# crypto_blk.net
KiCad netlist of a schematic drawn in Altium Designer
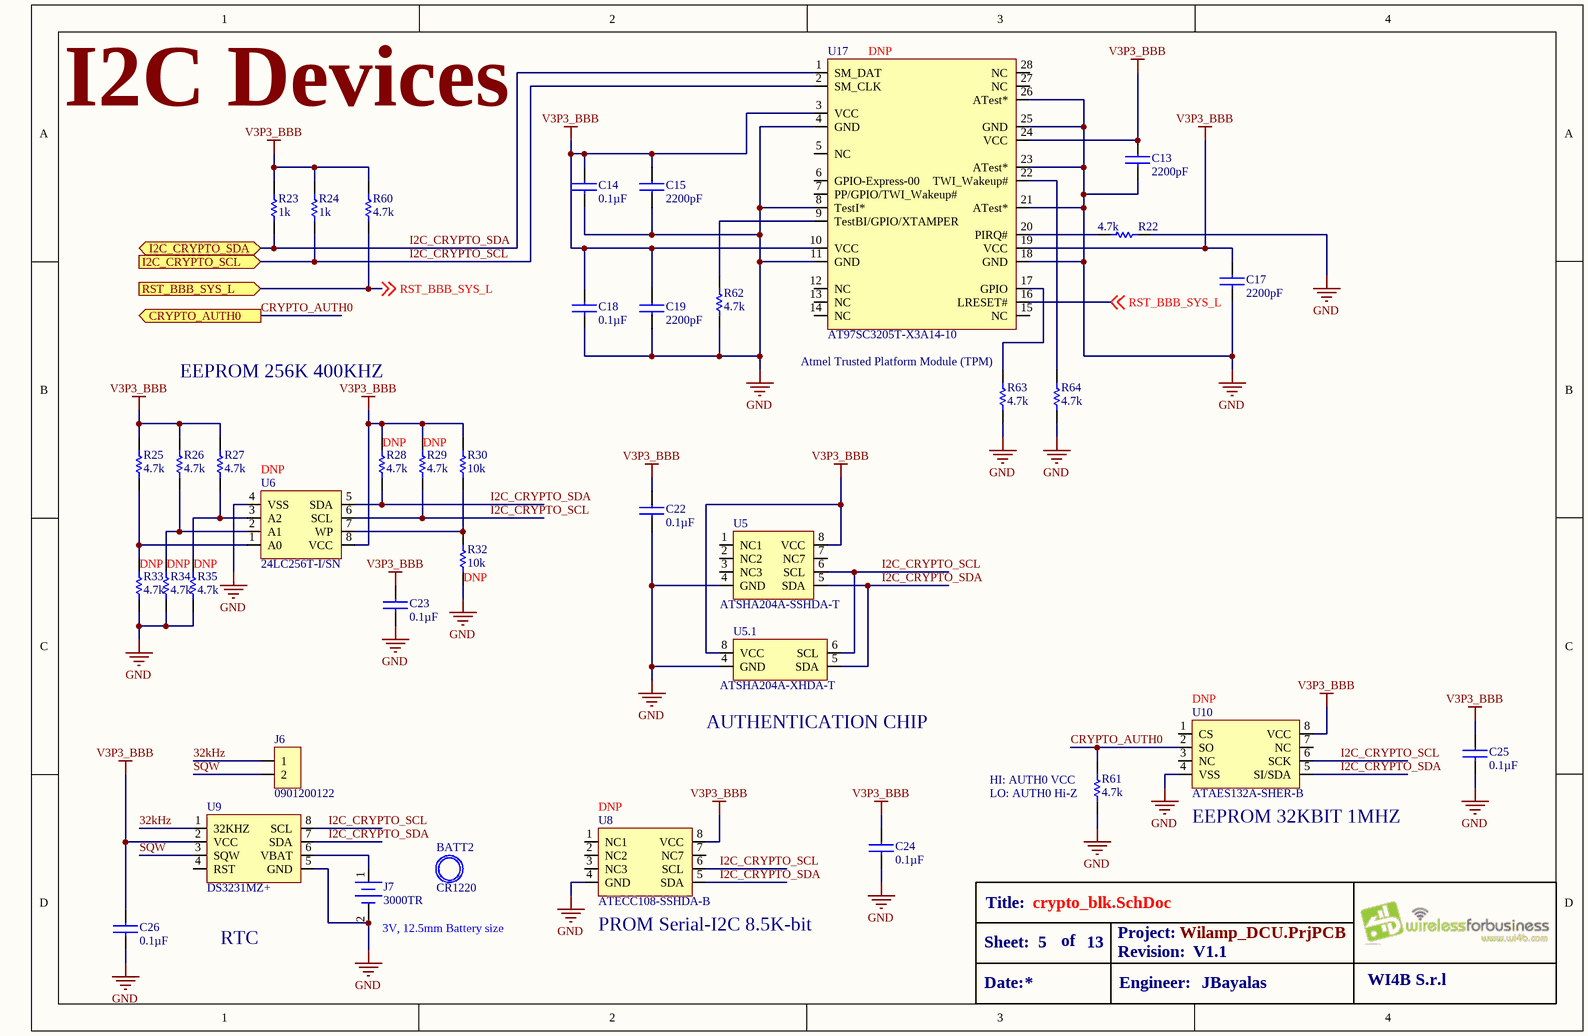
[diagram p0: crypto_blk.SchDoc]

(export (version "E")
  (design (tool "Eeschema 10.0.6"))
  (components
    (comp (ref "BATT2")
      (value "CR1220")
      (description "Coin Cell Battery 35mAh 12.5mm")
      (fields (field (name "MPN") "CR1220"))
      (libsource (lib "Miscellaneous") (part "CR1220"))
    )
    (comp (ref "C13")
      (value "2200pF")
      (footprint "C0805")
      (description "CAP CER 2200PF 50V 10% X7R 0805")
      (fields (field (name "MPN") "08055C222KAT2A"))
      (libsource (lib "Capacitor") (part "08055C222KAT2A"))
    )
    (comp (ref "C14")
      (value "0.1µF")
      (footprint "C0402")
      (description "CAP CER 0.1UF 16V X7R 0402")
      (fields (field (name "MPN") "CL05B104KO3LNNC"))
      (libsource (lib "Capacitor") (part "CL05B104KO3LNNC"))
    )
    (comp (ref "C15")
      (value "2200pF")
      (footprint "C0805")
      (description "CAP CER 2200PF 50V 10% X7R 0805")
      (fields (field (name "MPN") "08055C222KAT2A"))
      (libsource (lib "Capacitor") (part "08055C222KAT2A"))
    )
    (comp (ref "C17")
      (value "2200pF")
      (footprint "C0603")
      (description "CAP CER 2200PF 50V X7R 0603")
      (fields (field (name "MPN") "C0603C222K5RACTU"))
      (libsource (lib "Capacitor") (part "C0603C222K5RACTU"))
    )
    (comp (ref "C18")
      (value "0.1µF")
      (footprint "C0402")
      (description "CAP CER 0.1UF 16V X7R 0402")
      (fields (field (name "MPN") "CL05B104KO3LNNC"))
      (libsource (lib "Capacitor") (part "CL05B104KO3LNNC"))
    )
    (comp (ref "C19")
      (value "2200pF")
      (footprint "C0805")
      (description "CAP CER 2200PF 50V 10% X7R 0805")
      (fields (field (name "MPN") "08055C222KAT2A"))
      (libsource (lib "Capacitor") (part "08055C222KAT2A"))
    )
    (comp (ref "C22")
      (value "0.1µF")
      (footprint "C0402")
      (description "CAP CER 0.1UF 16V X7R 0402")
      (fields (field (name "MPN") "CL05B104KO3LNNC"))
      (libsource (lib "Capacitor") (part "CL05B104KO3LNNC"))
    )
    (comp (ref "C23")
      (value "0.1µF")
      (footprint "C0402")
      (description "CAP CER 0.1UF 16V X7R 0402")
      (fields (field (name "MPN") "CL05B104KO3LNNC"))
      (libsource (lib "Capacitor") (part "CL05B104KO3LNNC"))
    )
    (comp (ref "C24")
      (value "0.1µF")
      (footprint "C0402")
      (description "CAP CER 0.1UF 16V X7R 0402")
      (fields (field (name "MPN") "CL05B104KO3LNNC"))
      (libsource (lib "Capacitor") (part "CL05B104KO3LNNC"))
    )
    (comp (ref "C25")
      (value "0.1µF")
      (footprint "C0402")
      (description "CAP CER 0.1UF 16V X7R 0402")
      (fields (field (name "MPN") "CL05B104KO3LNNC"))
      (libsource (lib "Capacitor") (part "CL05B104KO3LNNC"))
    )
    (comp (ref "C26")
      (value "0.1µF")
      (footprint "C0402")
      (description "CAP CER 0.1UF 16V X7R 0402")
      (fields (field (name "MPN") "CL05B104KO3LNNC"))
      (libsource (lib "Capacitor") (part "CL05B104KO3LNNC"))
    )
    (comp (ref "J6")
      (value "*")
      (footprint "0901200122")
      (description "CONN HEADER 2POS .100\" STR TIN")
      (fields (field (name "MPN") "0901200122"))
      (libsource (lib "Connector") (part "0901200122"))
    )
    (comp (ref "J7")
      (value "3000TR")
      (footprint "3000TR")
      (description "Coin Cell Battery Holders SM COIN CELL B/H")
      (libsource (lib "Connector") (part "3000TR"))
    )
    (comp (ref "R22")
      (value "4.7k")
      (footprint "R0402")
      (description "RES SMD 4.7K OHM 5% 1/16W 0402")
      (fields (field (name "MPN") "RC0402JR-074K7L"))
      (libsource (lib "Res") (part "RC0402JR-074K7L"))
    )
    (comp (ref "R23")
      (value "1k")
      (footprint "R0402")
      (description "RES SMD 1K OHM 1% 1/10W 0402")
      (fields (field (name "MPN") "MCS04020C1001FE000"))
      (libsource (lib "Res") (part "MCS04020C1001FE000"))
    )
    (comp (ref "R24")
      (value "1k")
      (footprint "R0402")
      (description "RES SMD 1K OHM 1% 1/10W 0402")
      (fields (field (name "MPN") "MCS04020C1001FE000"))
      (libsource (lib "Res") (part "MCS04020C1001FE000"))
    )
    (comp (ref "R25")
      (value "4.7k")
      (footprint "R0402")
      (description "RES SMD 4.7K OHM 5% 1/16W 0402")
      (fields (field (name "MPN") "RC0402JR-074K7L"))
      (libsource (lib "Res") (part "RC0402JR-074K7L"))
    )
    (comp (ref "R26")
      (value "4.7k")
      (footprint "R0402")
      (description "RES SMD 4.7K OHM 5% 1/16W 0402")
      (fields (field (name "MPN") "RC0402JR-074K7L"))
      (libsource (lib "Res") (part "RC0402JR-074K7L"))
    )
    (comp (ref "R27")
      (value "4.7k")
      (footprint "R0402")
      (description "RES SMD 4.7K OHM 5% 1/16W 0402")
      (fields (field (name "MPN") "RC0402JR-074K7L"))
      (libsource (lib "Res") (part "RC0402JR-074K7L"))
    )
    (comp (ref "R28")
      (value "4.7k")
      (footprint "R0402")
      (description "RES SMD 4.7K OHM 5% 1/16W 0402")
      (fields (field (name "MPN") "RC0402JR-074K7L") (field (name "LOAD") "DNP"))
      (libsource (lib "Res") (part "RC0402JR-074K7L"))
    )
    (comp (ref "R29")
      (value "4.7k")
      (footprint "R0402")
      (description "RES SMD 4.7K OHM 5% 1/16W 0402")
      (fields (field (name "MPN") "RC0402JR-074K7L") (field (name "LOAD") "DNP"))
      (libsource (lib "Res") (part "RC0402JR-074K7L"))
    )
    (comp (ref "R30")
      (value "10k")
      (footprint "R0402")
      (description "RES SMD 10K OHM 1% 1/5W 0402")
      (fields (field (name "MPN") "CRCW040210K0FKEDHP"))
      (libsource (lib "Res") (part "CRCW040210K0FKEDHP"))
    )
    (comp (ref "R32")
      (value "10k")
      (footprint "R0402")
      (description "RES SMD 10K OHM 1% 1/5W 0402")
      (fields (field (name "MPN") "CRCW040210K0FKEDHP") (field (name "LOAD") "DNP"))
      (libsource (lib "Res") (part "CRCW040210K0FKEDHP"))
    )
    (comp (ref "R33")
      (value "4.7k")
      (footprint "R0402")
      (description "RES SMD 4.7K OHM 5% 1/16W 0402")
      (fields (field (name "MPN") "RC0402JR-074K7L") (field (name "LOAD") "DNP"))
      (libsource (lib "Res") (part "RC0402JR-074K7L"))
    )
    (comp (ref "R34")
      (value "4.7k")
      (footprint "R0402")
      (description "RES SMD 4.7K OHM 5% 1/16W 0402")
      (fields (field (name "MPN") "RC0402JR-074K7L") (field (name "LOAD") "DNP"))
      (libsource (lib "Res") (part "RC0402JR-074K7L"))
    )
    (comp (ref "R35")
      (value "4.7k")
      (footprint "R0402")
      (description "RES SMD 4.7K OHM 5% 1/16W 0402")
      (fields (field (name "MPN") "RC0402JR-074K7L") (field (name "LOAD") "DNP"))
      (libsource (lib "Res") (part "RC0402JR-074K7L"))
    )
    (comp (ref "R60")
      (value "4.7k")
      (footprint "R0402")
      (description "RES SMD 4.7K OHM 5% 1/16W 0402")
      (fields (field (name "MPN") "RC0402JR-074K7L"))
      (libsource (lib "Res") (part "RC0402JR-074K7L"))
    )
    (comp (ref "R61")
      (value "4.7k")
      (footprint "R0402")
      (description "RES SMD 4.7K OHM 5% 1/16W 0402")
      (fields (field (name "MPN") "RC0402JR-074K7L"))
      (libsource (lib "Res") (part "RC0402JR-074K7L"))
    )
    (comp (ref "R62")
      (value "4.7k")
      (footprint "R0402")
      (description "RES SMD 4.7K OHM 5% 1/16W 0402")
      (fields (field (name "MPN") "RC0402JR-074K7L"))
      (libsource (lib "Res") (part "RC0402JR-074K7L"))
    )
    (comp (ref "R63")
      (value "4.7k")
      (footprint "R0402")
      (description "RES SMD 4.7K OHM 5% 1/16W 0402")
      (fields (field (name "MPN") "RC0402JR-074K7L"))
      (libsource (lib "Res") (part "RC0402JR-074K7L"))
    )
    (comp (ref "R64")
      (value "4.7k")
      (footprint "R0402")
      (description "RES SMD 4.7K OHM 5% 1/16W 0402")
      (fields (field (name "MPN") "RC0402JR-074K7L"))
      (libsource (lib "Res") (part "RC0402JR-074K7L"))
    )
    (comp (ref "U5")
      (value "ATSHA204A-SSHDA-T")
      (footprint "SOIC-8")
      (description "IC AUTHENTICATION CHIP 8SOIC")
      (libsource (lib "IC") (part "ATSHA204A-SSHDA-T"))
    )
    (comp (ref "U5.1")
      (value "ATSHA204A-XHDA-T")
      (footprint "TSSOP-8 (wide Body)")
      (description "IC CRYPTO 4.5KB I2C")
      (fields (field (name "MPN") "ATSHA204A-XHDA-T"))
      (libsource (lib "IC") (part "ATSHA204A-XHDA-T"))
    )
    (comp (ref "U6")
      (value "24LC256T-I/SN")
      (footprint "SOIC-8")
      (description "IC EEPROM 256K I2C 400KHZ 8SOIC")
      (fields (field (name "LOAD") "DNP"))
      (libsource (lib "IC") (part "24LC256T-I/SN"))
    )
    (comp (ref "U8")
      (value "ATECC108-SSHDA-B")
      (footprint "SOIC-8")
      (description "EEPROM Serial-I2C 8.5K-bit 2.5V/3.3V/5V 8-Pin SOIC Bulk")
      (fields (field (name "LOAD") "DNP"))
      (libsource (lib "IC") (part "ATECC108-SSHDA-B"))
    )
    (comp (ref "U9")
      (value "DS3231MZ+")
      (footprint "SOIC-8")
      (description "IC RTC I2C 8SOIC")
      (libsource (lib "IC") (part "DS3231MZ+"))
    )
    (comp (ref "U10")
      (value "ATAES132A-SHER-B")
      (footprint "SOIC-8")
      (description "IC EEPROM 32KBIT 1MHZ 8SOIC")
      (fields (field (name "LOAD") "DNP"))
      (libsource (lib "IC") (part "ATAES132A-SHER-B"))
    )
    (comp (ref "U17")
      (value "AT97SC3205T-X3A14-10")
      (footprint "TSSOP-28")
      (description "STD COM 12C TPM 4.4 MM TSSOP UEK")
      (fields (field (name "LOAD") "DNP"))
      (libsource (lib "IC") (part "AT97SC3205T-X3A14-10"))
    )
  )
  (nets
    (net (code "1") (name "/32kHz") (class "Default")
      (node (ref "J6") (pin "1") (pinfunction "1_1") (pintype "passive"))
      (node (ref "U9") (pin "1") (pinfunction "32KHZ_1") (pintype "passive"))
    )
    (net (code "2") (name "/CRYPTO_AUTH0") (class "Default")
      (node (ref "R61") (pin "2") (pinfunction "2_2") (pintype "passive"))
      (node (ref "U10") (pin "2") (pinfunction "SO_2") (pintype "passive"))
    )
    (net (code "3") (name "/I2C_CRYPTO_SCL") (class "Default")
      (node (ref "R24") (pin "2") (pinfunction "2_2") (pintype "passive"))
      (node (ref "R29") (pin "1") (pinfunction "1_1") (pintype "passive"))
      (node (ref "U10") (pin "6") (pinfunction "SCK_6") (pintype "passive"))
      (node (ref "U17") (pin "2") (pinfunction "SM_CLK_2") (pintype "passive"))
      (node (ref "U5") (pin "6") (pinfunction "SCL_6") (pintype "passive"))
      (node (ref "U5.1") (pin "6") (pinfunction "SCL_6") (pintype "passive"))
      (node (ref "U6") (pin "6") (pinfunction "SCL_6") (pintype "passive"))
      (node (ref "U8") (pin "6") (pinfunction "SCL_6") (pintype "passive"))
      (node (ref "U9") (pin "8") (pinfunction "SCL_8") (pintype "passive"))
    )
    (net (code "4") (name "/I2C_CRYPTO_SDA") (class "Default")
      (node (ref "R23") (pin "2") (pinfunction "2_2") (pintype "passive"))
      (node (ref "R28") (pin "1") (pinfunction "1_1") (pintype "passive"))
      (node (ref "U10") (pin "5") (pinfunction "SI/SDA_5") (pintype "passive"))
      (node (ref "U17") (pin "1") (pinfunction "SM_DAT_1") (pintype "passive"))
      (node (ref "U5") (pin "5") (pinfunction "SDA_5") (pintype "passive"))
      (node (ref "U5.1") (pin "5") (pinfunction "SDA_5") (pintype "passive"))
      (node (ref "U6") (pin "5") (pinfunction "SDA_5") (pintype "passive"))
      (node (ref "U8") (pin "5") (pinfunction "SDA_5") (pintype "passive"))
      (node (ref "U9") (pin "7") (pinfunction "SDA_7") (pintype "passive"))
    )
    (net (code "5") (name "/SQW") (class "Default")
      (node (ref "J6") (pin "2") (pinfunction "2_2") (pintype "passive"))
      (node (ref "U9") (pin "3") (pinfunction "SQW_3") (pintype "passive"))
    )
    (net (code "6") (name "GND") (class "Default")
      (node (ref "C13") (pin "2") (pinfunction "2_2") (pintype "passive"))
      (node (ref "C14") (pin "2") (pinfunction "2_2") (pintype "passive"))
      (node (ref "C15") (pin "2") (pinfunction "2_2") (pintype "passive"))
      (node (ref "C17") (pin "2") (pinfunction "2_2") (pintype "passive"))
      (node (ref "C18") (pin "2") (pinfunction "2_2") (pintype "passive"))
      (node (ref "C19") (pin "2") (pinfunction "2_2") (pintype "passive"))
      (node (ref "C22") (pin "2") (pinfunction "2_2") (pintype "passive"))
      (node (ref "C23") (pin "2") (pinfunction "2_2") (pintype "passive"))
      (node (ref "C24") (pin "2") (pinfunction "2_2") (pintype "passive"))
      (node (ref "C25") (pin "2") (pinfunction "2_2") (pintype "passive"))
      (node (ref "C26") (pin "2") (pinfunction "2_2") (pintype "passive"))
      (node (ref "J7") (pin "2") (pinfunction "-_2") (pintype "passive"))
      (node (ref "R22") (pin "1") (pinfunction "1_1") (pintype "passive"))
      (node (ref "R32") (pin "1") (pinfunction "1_1") (pintype "passive"))
      (node (ref "R33") (pin "1") (pinfunction "1_1") (pintype "passive"))
      (node (ref "R34") (pin "1") (pinfunction "1_1") (pintype "passive"))
      (node (ref "R35") (pin "1") (pinfunction "1_1") (pintype "passive"))
      (node (ref "R61") (pin "1") (pinfunction "1_1") (pintype "passive"))
      (node (ref "R62") (pin "1") (pinfunction "1_1") (pintype "passive"))
      (node (ref "R63") (pin "1") (pinfunction "1_1") (pintype "passive"))
      (node (ref "R64") (pin "1") (pinfunction "1_1") (pintype "passive"))
      (node (ref "U10") (pin "4") (pinfunction "VSS_4") (pintype "passive"))
      (node (ref "U17") (pin "11") (pinfunction "GND_11") (pintype "passive"))
      (node (ref "U17") (pin "18") (pinfunction "GND_18") (pintype "passive"))
      (node (ref "U17") (pin "21") (pinfunction "ATest*_21") (pintype "passive"))
      (node (ref "U17") (pin "23") (pinfunction "ATest*_23") (pintype "passive"))
      (node (ref "U17") (pin "25") (pinfunction "GND_25") (pintype "passive"))
      (node (ref "U17") (pin "26") (pinfunction "ATest*_26") (pintype "passive"))
      (node (ref "U17") (pin "4") (pinfunction "GND_4") (pintype "passive"))
      (node (ref "U17") (pin "8") (pinfunction "TestI*_8") (pintype "passive"))
      (node (ref "U5") (pin "4") (pinfunction "GND_4") (pintype "passive"))
      (node (ref "U5.1") (pin "4") (pinfunction "GND_4") (pintype "passive"))
      (node (ref "U6") (pin "4") (pinfunction "VSS_4") (pintype "passive"))
      (node (ref "U8") (pin "4") (pinfunction "GND_4") (pintype "passive"))
      (node (ref "U9") (pin "5") (pinfunction "GND_5") (pintype "passive"))
    )
    (net (code "7") (name "Net-(J7-+)") (class "Default")
      (node (ref "J7") (pin "1") (pinfunction "+_1") (pintype "passive"))
      (node (ref "U9") (pin "6") (pinfunction "VBAT_6") (pintype "passive"))
    )
    (net (code "8") (name "Net-(U6-A0)") (class "Default")
      (node (ref "R25") (pin "1") (pinfunction "1_1") (pintype "passive"))
      (node (ref "R33") (pin "2") (pinfunction "2_2") (pintype "passive"))
      (node (ref "U6") (pin "1") (pinfunction "A0_1") (pintype "passive"))
    )
    (net (code "9") (name "Net-(U6-A1)") (class "Default")
      (node (ref "R26") (pin "1") (pinfunction "1_1") (pintype "passive"))
      (node (ref "R34") (pin "2") (pinfunction "2_2") (pintype "passive"))
      (node (ref "U6") (pin "2") (pinfunction "A1_2") (pintype "passive"))
    )
    (net (code "10") (name "Net-(U6-A2)") (class "Default")
      (node (ref "R27") (pin "1") (pinfunction "1_1") (pintype "passive"))
      (node (ref "R35") (pin "2") (pinfunction "2_2") (pintype "passive"))
      (node (ref "U6") (pin "3") (pinfunction "A2_3") (pintype "passive"))
    )
    (net (code "11") (name "Net-(U6-WP)") (class "Default")
      (node (ref "R30") (pin "1") (pinfunction "1_1") (pintype "passive"))
      (node (ref "R32") (pin "2") (pinfunction "2_2") (pintype "passive"))
      (node (ref "U6") (pin "7") (pinfunction "WP_7") (pintype "passive"))
    )
    (net (code "12") (name "Net-(U17-GPIO)") (class "Default")
      (node (ref "R63") (pin "2") (pinfunction "2_2") (pintype "passive"))
      (node (ref "U17") (pin "17") (pinfunction "GPIO_17") (pintype "passive"))
    )
    (net (code "13") (name "Net-(U17-PIRQ#)") (class "Default")
      (node (ref "R22") (pin "2") (pinfunction "2_2") (pintype "passive"))
      (node (ref "U17") (pin "20") (pinfunction "PIRQ#_20") (pintype "passive"))
    )
    (net (code "14") (name "Net-(U17-TWI_Wakeup#)") (class "Default")
      (node (ref "R64") (pin "2") (pinfunction "2_2") (pintype "passive"))
      (node (ref "U17") (pin "22") (pinfunction "TWI_Wakeup#_22") (pintype "passive"))
    )
    (net (code "15") (name "Net-(U17-TestBI{slash}GPIO{slash}XTAMPER)") (class "Default")
      (node (ref "R62") (pin "2") (pinfunction "2_2") (pintype "passive"))
      (node (ref "U17") (pin "9") (pinfunction "TestBI/GPIO/XTAMPER_9") (pintype "passive"))
    )
    (net (code "16") (name "RST_BBB_SYS_L") (class "Default")
      (node (ref "R60") (pin "1") (pinfunction "1_1") (pintype "passive"))
      (node (ref "U17") (pin "16") (pinfunction "LRESET#_16") (pintype "passive"))
    )
    (net (code "17") (name "V3P3_BBB") (class "Default")
      (node (ref "C13") (pin "1") (pinfunction "1_1") (pintype "passive"))
      (node (ref "C14") (pin "1") (pinfunction "1_1") (pintype "passive"))
      (node (ref "C15") (pin "1") (pinfunction "1_1") (pintype "passive"))
      (node (ref "C17") (pin "1") (pinfunction "1_1") (pintype "passive"))
      (node (ref "C18") (pin "1") (pinfunction "1_1") (pintype "passive"))
      (node (ref "C19") (pin "1") (pinfunction "1_1") (pintype "passive"))
      (node (ref "C22") (pin "1") (pinfunction "1_1") (pintype "passive"))
      (node (ref "C23") (pin "1") (pinfunction "1_1") (pintype "passive"))
      (node (ref "C24") (pin "1") (pinfunction "1_1") (pintype "passive"))
      (node (ref "C25") (pin "1") (pinfunction "1_1") (pintype "passive"))
      (node (ref "C26") (pin "1") (pinfunction "1_1") (pintype "passive"))
      (node (ref "R23") (pin "1") (pinfunction "1_1") (pintype "passive"))
      (node (ref "R24") (pin "1") (pinfunction "1_1") (pintype "passive"))
      (node (ref "R25") (pin "2") (pinfunction "2_2") (pintype "passive"))
      (node (ref "R26") (pin "2") (pinfunction "2_2") (pintype "passive"))
      (node (ref "R27") (pin "2") (pinfunction "2_2") (pintype "passive"))
      (node (ref "R28") (pin "2") (pinfunction "2_2") (pintype "passive"))
      (node (ref "R29") (pin "2") (pinfunction "2_2") (pintype "passive"))
      (node (ref "R30") (pin "2") (pinfunction "2_2") (pintype "passive"))
      (node (ref "R60") (pin "2") (pinfunction "2_2") (pintype "passive"))
      (node (ref "U10") (pin "8") (pinfunction "VCC_8") (pintype "passive"))
      (node (ref "U17") (pin "10") (pinfunction "VCC_10") (pintype "passive"))
      (node (ref "U17") (pin "19") (pinfunction "VCC_19") (pintype "passive"))
      (node (ref "U17") (pin "24") (pinfunction "VCC_24") (pintype "passive"))
      (node (ref "U17") (pin "3") (pinfunction "VCC_3") (pintype "passive"))
      (node (ref "U5") (pin "8") (pinfunction "VCC_8") (pintype "passive"))
      (node (ref "U5.1") (pin "8") (pinfunction "VCC_8") (pintype "passive"))
      (node (ref "U6") (pin "8") (pinfunction "VCC_8") (pintype "passive"))
      (node (ref "U8") (pin "8") (pinfunction "VCC_8") (pintype "passive"))
      (node (ref "U9") (pin "2") (pinfunction "VCC_2") (pintype "passive"))
    )
    (net (code "18") (name "unconnected-(U5-NC1-Pad1)") (class "Default")
      (node (ref "U5") (pin "1") (pinfunction "NC1_1") (pintype "passive"))
    )
    (net (code "19") (name "unconnected-(U5-NC2-Pad2)") (class "Default")
      (node (ref "U5") (pin "2") (pinfunction "NC2_2") (pintype "passive"))
    )
    (net (code "20") (name "unconnected-(U5-NC3-Pad3)") (class "Default")
      (node (ref "U5") (pin "3") (pinfunction "NC3_3") (pintype "passive"))
    )
    (net (code "21") (name "unconnected-(U5-NC7-Pad7)") (class "Default")
      (node (ref "U5") (pin "7") (pinfunction "NC7_7") (pintype "passive"))
    )
    (net (code "22") (name "unconnected-(U8-NC1-Pad1)") (class "Default")
      (node (ref "U8") (pin "1") (pinfunction "NC1_1") (pintype "passive"))
    )
    (net (code "23") (name "unconnected-(U8-NC2-Pad2)") (class "Default")
      (node (ref "U8") (pin "2") (pinfunction "NC2_2") (pintype "passive"))
    )
    (net (code "24") (name "unconnected-(U8-NC3-Pad3)") (class "Default")
      (node (ref "U8") (pin "3") (pinfunction "NC3_3") (pintype "passive"))
    )
    (net (code "25") (name "unconnected-(U8-NC7-Pad7)") (class "Default")
      (node (ref "U8") (pin "7") (pinfunction "NC7_7") (pintype "passive"))
    )
    (net (code "26") (name "unconnected-(U9-RST-Pad4)") (class "Default")
      (node (ref "U9") (pin "4") (pinfunction "RST_4") (pintype "passive"))
    )
    (net (code "27") (name "unconnected-(U10-CS-Pad1)") (class "Default")
      (node (ref "U10") (pin "1") (pinfunction "CS_1") (pintype "passive"))
    )
    (net (code "28") (name "unconnected-(U10-NC-Pad3)") (class "Default")
      (node (ref "U10") (pin "3") (pinfunction "NC_3") (pintype "passive"))
    )
    (net (code "29") (name "unconnected-(U10-NC-Pad7)") (class "Default")
      (node (ref "U10") (pin "7") (pinfunction "NC_7") (pintype "passive"))
    )
    (net (code "30") (name "unconnected-(U17-GPIO-Express-00-Pad6)") (class "Default")
      (node (ref "U17") (pin "6") (pinfunction "GPIO-Express-00_6") (pintype "passive"))
    )
    (net (code "31") (name "unconnected-(U17-NC-Pad5)") (class "Default")
      (node (ref "U17") (pin "5") (pinfunction "NC_5") (pintype "passive"))
    )
    (net (code "32") (name "unconnected-(U17-NC-Pad12)") (class "Default")
      (node (ref "U17") (pin "12") (pinfunction "NC_12") (pintype "passive"))
    )
    (net (code "33") (name "unconnected-(U17-NC-Pad13)") (class "Default")
      (node (ref "U17") (pin "13") (pinfunction "NC_13") (pintype "passive"))
    )
    (net (code "34") (name "unconnected-(U17-NC-Pad14)") (class "Default")
      (node (ref "U17") (pin "14") (pinfunction "NC_14") (pintype "passive"))
    )
    (net (code "35") (name "unconnected-(U17-NC-Pad15)") (class "Default")
      (node (ref "U17") (pin "15") (pinfunction "NC_15") (pintype "passive"))
    )
    (net (code "36") (name "unconnected-(U17-NC-Pad27)") (class "Default")
      (node (ref "U17") (pin "27") (pinfunction "NC_27") (pintype "passive"))
    )
    (net (code "37") (name "unconnected-(U17-NC-Pad28)") (class "Default")
      (node (ref "U17") (pin "28") (pinfunction "NC_28") (pintype "passive"))
    )
    (net (code "38") (name "unconnected-(U17-PP{slash}GPIO{slash}TWI_Wakeup#-Pad7)") (class "Default")
      (node (ref "U17") (pin "7") (pinfunction "PP/GPIO/TWI_Wakeup#_7") (pintype "passive"))
    )
  )
)
